# HDMI.net
KiCad netlist of a schematic drawn in Altium Designer
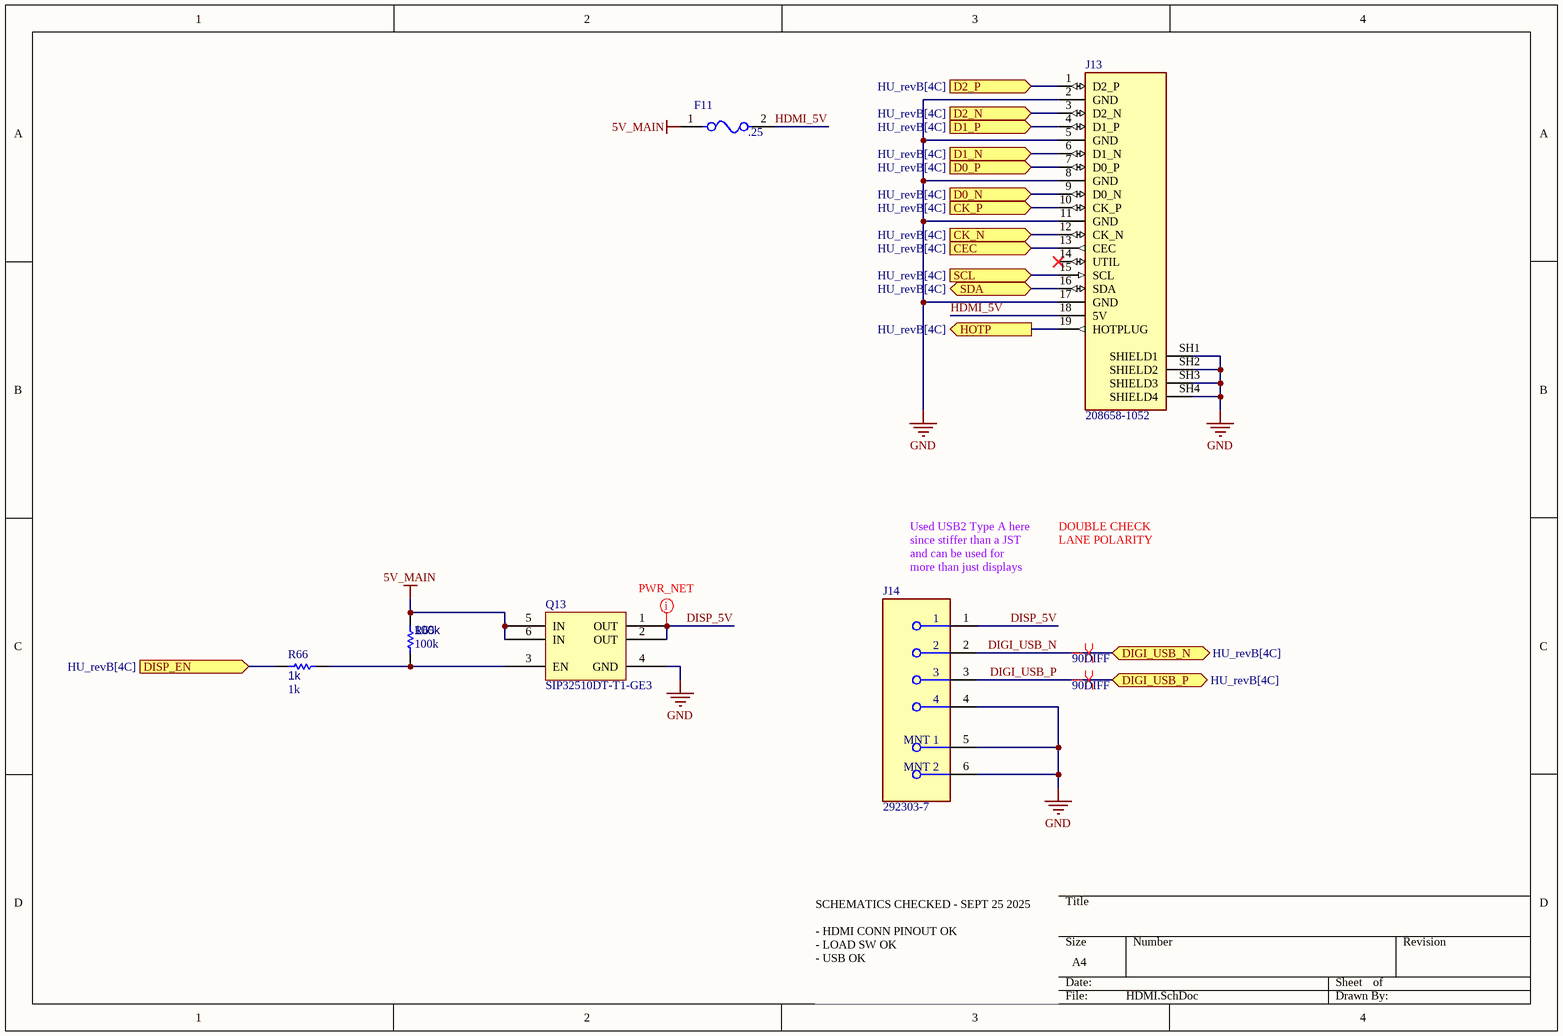
[diagram p0: HDMI.SchDoc]

(export (version "E")
  (design (tool "Eeschema 10.0.6"))
  (components
    (comp (ref "F11")
      (value ".25")
      (footprint "FP-0685T-MFG")
      (description "FUSE BOARD MNT 5A 63VAC/VDC 1206")
      (libsource (lib "Altium Content Vault") (part "5bcf9b9f640e542cf0359d10258e979"))
    )
    (comp (ref "J13")
      (value "208658-1052")
      (footprint "208658-1052-Footprint-1")
      (description "HDMI CONNECTOR, RCPT, 19POS, SMT; Available until stocks are exhausted Alternative available")
      (libsource (lib "Space Concordia") (part "208658-1052"))
    )
    (comp (ref "J14")
      (value "292303-7")
      (footprint "FP-292303-7-MFG")
      (description "CONN RCPT USB2.0 TYPEA 4P SMD RA")
      (fields
        (field (name "OCTOPART") "https://octopart.com/292303-7-te+connectivity-42840369")
        (field (name "MANUFACTURER") "TE Connectivity")
      )
      (libsource (lib "Altium Content Vault") (part "79e6714efa0bb2f851c24b2688127c9"))
    )
    (comp (ref "Q13")
      (value "SIP32510DT-T1-GE3")
      (footprint "SOT95P284X110-6N")
      (description "Power Switch ICs – Power Distribution; VISHAY; SIP32510DT-T1-GE3; 1; 1; 5.5 V; SOT-23-6")
      (libsource (lib "Space Concordia") (part "SIP32510DT-T1-GE3"))
    )
    (comp (ref "R65")
      (value "100k")
      (footprint "R0603B")
      (description "Resistor")
      (fields (field (name "ALTIUM_VALUE") "100k"))
      (libsource (lib "Space Concordia") (part "Resistor"))
    )
    (comp (ref "R66")
      (value "1k")
      (footprint "R0603B")
      (description "Resistor")
      (fields (field (name "ALTIUM_VALUE") "1k"))
      (libsource (lib "Space Concordia") (part "Resistor"))
    )
  )
  (nets
    (net (code "1") (name "/CEC") (class "Default")
      (node (ref "J13") (pin "13") (pinfunction "CEC_13") (pintype "output"))
    )
    (net (code "2") (name "/CK_N") (class "Default")
      (node (ref "J13") (pin "12") (pinfunction "CK_N_12") (pintype "bidirectional"))
    )
    (net (code "3") (name "/CK_P") (class "Default")
      (node (ref "J13") (pin "10") (pinfunction "CK_P_10") (pintype "bidirectional"))
    )
    (net (code "4") (name "/D0_N") (class "Default")
      (node (ref "J13") (pin "9") (pinfunction "D0_N_9") (pintype "bidirectional"))
    )
    (net (code "5") (name "/D0_P") (class "Default")
      (node (ref "J13") (pin "7") (pinfunction "D0_P_7") (pintype "bidirectional"))
    )
    (net (code "6") (name "/D1_N") (class "Default")
      (node (ref "J13") (pin "6") (pinfunction "D1_N_6") (pintype "bidirectional"))
    )
    (net (code "7") (name "/D1_P") (class "Default")
      (node (ref "J13") (pin "4") (pinfunction "D1_P_4") (pintype "bidirectional"))
    )
    (net (code "8") (name "/D2_N") (class "Default")
      (node (ref "J13") (pin "3") (pinfunction "D2_N_3") (pintype "bidirectional"))
    )
    (net (code "9") (name "/D2_P") (class "Default")
      (node (ref "J13") (pin "1") (pinfunction "D2_P_1") (pintype "bidirectional"))
    )
    (net (code "10") (name "/DIGI_USB_N") (class "Default")
      (node (ref "J14") (pin "2") (pinfunction "2_2") (pintype "passive"))
    )
    (net (code "11") (name "/DIGI_USB_P") (class "Default")
      (node (ref "J14") (pin "3") (pinfunction "3_3") (pintype "passive"))
    )
    (net (code "12") (name "/DISP_5V") (class "Default")
      (node (ref "J14") (pin "1") (pinfunction "1_1") (pintype "passive"))
      (node (ref "Q13") (pin "1") (pinfunction "OUT_1") (pintype "passive"))
      (node (ref "Q13") (pin "2") (pinfunction "OUT_2") (pintype "passive"))
    )
    (net (code "13") (name "/DISP_EN") (class "Default")
      (node (ref "R66") (pin "2") (pinfunction "2_2") (pintype "passive"))
    )
    (net (code "14") (name "/HDMI_5V") (class "Default")
      (node (ref "F11") (pin "2") (pinfunction "2_2") (pintype "passive"))
      (node (ref "J13") (pin "18") (pinfunction "5V_18") (pintype "passive"))
    )
    (net (code "15") (name "/HOTP") (class "Default")
      (node (ref "J13") (pin "19") (pinfunction "HOTPLUG_19") (pintype "output"))
    )
    (net (code "16") (name "/SCL") (class "Default")
      (node (ref "J13") (pin "15") (pinfunction "SCL_15") (pintype "input"))
    )
    (net (code "17") (name "/SDA") (class "Default")
      (node (ref "J13") (pin "16") (pinfunction "SDA_16") (pintype "bidirectional"))
    )
    (net (code "18") (name "5V_MAIN") (class "Default")
      (node (ref "F11") (pin "1") (pinfunction "1_1") (pintype "passive"))
      (node (ref "Q13") (pin "5") (pinfunction "IN_5") (pintype "passive"))
      (node (ref "Q13") (pin "6") (pinfunction "IN_6") (pintype "passive"))
      (node (ref "R65") (pin "2") (pinfunction "2_2") (pintype "passive"))
    )
    (net (code "19") (name "GND") (class "Default")
      (node (ref "J13") (pin "11") (pinfunction "GND_11") (pintype "passive"))
      (node (ref "J13") (pin "17") (pinfunction "GND_17") (pintype "passive"))
      (node (ref "J13") (pin "2") (pinfunction "GND_2") (pintype "passive"))
      (node (ref "J13") (pin "5") (pinfunction "GND_5") (pintype "passive"))
      (node (ref "J13") (pin "8") (pinfunction "GND_8") (pintype "passive"))
      (node (ref "J13") (pin "SH1") (pinfunction "SHIELD1_SH1") (pintype "passive"))
      (node (ref "J13") (pin "SH2") (pinfunction "SHIELD2_SH2") (pintype "passive"))
      (node (ref "J13") (pin "SH3") (pinfunction "SHIELD3_SH3") (pintype "passive"))
      (node (ref "J13") (pin "SH4") (pinfunction "SHIELD4_SH4") (pintype "passive"))
      (node (ref "J14") (pin "4") (pinfunction "4_4") (pintype "passive"))
      (node (ref "J14") (pin "5") (pinfunction "MNT_1_5") (pintype "passive"))
      (node (ref "J14") (pin "6") (pinfunction "MNT_2_6") (pintype "passive"))
      (node (ref "Q13") (pin "4") (pinfunction "GND_4") (pintype "passive"))
    )
    (net (code "20") (name "Net-(Q13-EN)") (class "Default")
      (node (ref "Q13") (pin "3") (pinfunction "EN_3") (pintype "passive"))
      (node (ref "R65") (pin "1") (pinfunction "1_1") (pintype "passive"))
      (node (ref "R66") (pin "1") (pinfunction "1_1") (pintype "passive"))
    )
    (net (code "21") (name "unconnected-(J13-UTIL-Pad14)") (class "Default")
      (node (ref "J13") (pin "14") (pinfunction "UTIL_14") (pintype "bidirectional+no_connect"))
    )
  )
)
